# MCU_IO.net
KiCad netlist of a schematic drawn in Altium Designer
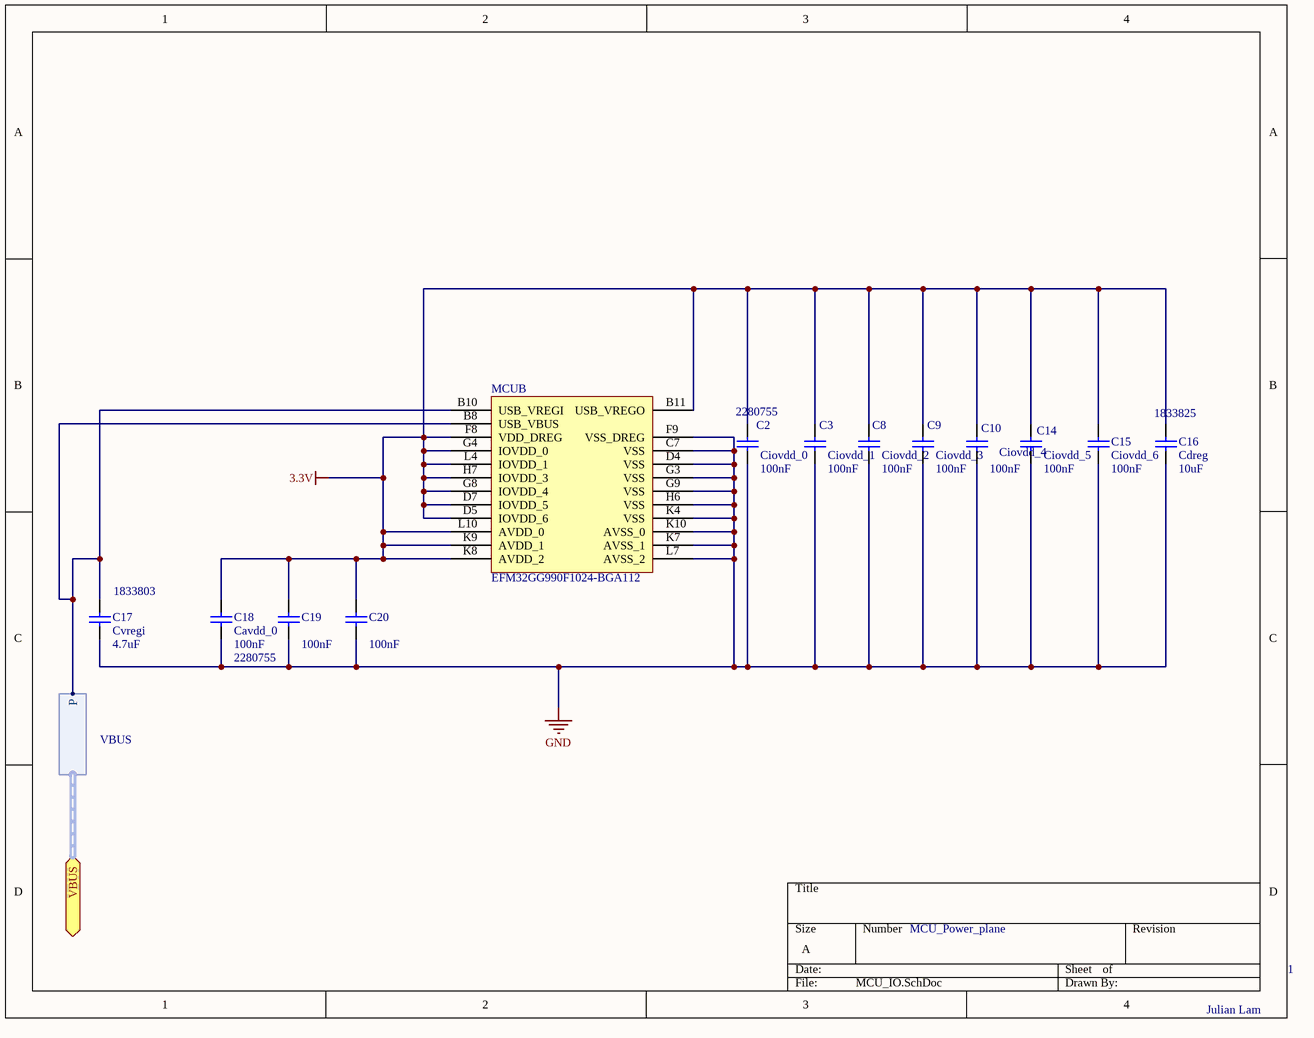
[diagram p0: MCU_IO.SchDoc]

(export (version "E")
  (design (tool "Eeschema 10.0.6"))
  (components
    (comp (ref "C2")
      (value "Ciovdd_0")
      (footprint "C1206")
      (description "Capacitor (Semiconductor SIM Model)")
      (fields
        (field (name "ALTIUM_VALUE") "100nF")
        (field (name "SUPPLIER PART NUMBER 1") "2280755")
        (field (name "MANUFACTURER") "AVX")
        (field (name "MANUFACTURER PART NUMBER") "02016D104KAT2A")
        (field (name "PUBLISHER") "Altium Limited")
      )
      (libsource (lib "Miscellaneous Devices") (part "Cap Semi"))
    )
    (comp (ref "C3")
      (value "Ciovdd_1")
      (footprint "C1206")
      (description "Capacitor (Semiconductor SIM Model)")
      (fields
        (field (name "ALTIUM_VALUE") "100nF")
        (field (name "MANUFACTURER") "AVX")
        (field (name "MANUFACTURER PART NUMBER") "02016D104KAT2A")
        (field (name "PUBLISHER") "Altium Limited")
      )
      (libsource (lib "Miscellaneous Devices") (part "Cap Semi"))
    )
    (comp (ref "C8")
      (value "Ciovdd_2")
      (footprint "C1206")
      (description "Capacitor (Semiconductor SIM Model)")
      (fields
        (field (name "ALTIUM_VALUE") "100nF")
        (field (name "MANUFACTURER") "AVX")
        (field (name "MANUFACTURER PART NUMBER") "02016D104KAT2A")
        (field (name "PUBLISHER") "Altium Limited")
      )
      (libsource (lib "Miscellaneous Devices") (part "Cap Semi"))
    )
    (comp (ref "C9")
      (value "Ciovdd_3")
      (footprint "C1206")
      (description "Capacitor (Semiconductor SIM Model)")
      (fields
        (field (name "ALTIUM_VALUE") "100nF")
        (field (name "MANUFACTURER") "AVX")
        (field (name "MANUFACTURER PART NUMBER") "02016D104KAT2A")
        (field (name "PUBLISHER") "Altium Limited")
      )
      (libsource (lib "Miscellaneous Devices") (part "Cap Semi"))
    )
    (comp (ref "C10")
      (value "Ciovdd_4")
      (footprint "C1206")
      (description "Capacitor (Semiconductor SIM Model)")
      (fields
        (field (name "ALTIUM_VALUE") "100nF")
        (field (name "MANUFACTURER") "AVX")
        (field (name "MANUFACTURER PART NUMBER") "02016D104KAT2A")
        (field (name "PUBLISHER") "Altium Limited")
      )
      (libsource (lib "Miscellaneous Devices") (part "Cap Semi"))
    )
    (comp (ref "C14")
      (value "Ciovdd_5")
      (footprint "C1206")
      (description "Capacitor (Semiconductor SIM Model)")
      (fields
        (field (name "ALTIUM_VALUE") "100nF")
        (field (name "MANUFACTURER") "AVX")
        (field (name "MANUFACTURER PART NUMBER") "02016D104KAT2A")
        (field (name "PUBLISHER") "Altium Limited")
      )
      (libsource (lib "Miscellaneous Devices") (part "Cap Semi"))
    )
    (comp (ref "C15")
      (value "Ciovdd_6")
      (footprint "C1206")
      (description "Capacitor (Semiconductor SIM Model)")
      (fields
        (field (name "ALTIUM_VALUE") "100nF")
        (field (name "MANUFACTURER") "AVX")
        (field (name "MANUFACTURER PART NUMBER") "02016D104KAT2A")
        (field (name "PUBLISHER") "Altium Limited")
      )
      (libsource (lib "Miscellaneous Devices") (part "Cap Semi"))
    )
    (comp (ref "C16")
      (value "Cdreg")
      (footprint "C1206")
      (description "Capacitor (Semiconductor SIM Model)")
      (fields
        (field (name "ALTIUM_VALUE") "10uF")
        (field (name "SUPPLIER PART NUMBER 1") "1833825")
        (field (name "MANUFACTURER") "AVX")
        (field (name "MANUFACTURER PART NUMBER") "12063D106KAT2A")
        (field (name "PUBLISHER") "Altium Limited")
      )
      (libsource (lib "Miscellaneous Devices") (part "Cap Semi"))
    )
    (comp (ref "C17")
      (value "Cvregi")
      (footprint "C1206")
      (description "Capacitor (Semiconductor SIM Model)")
      (fields
        (field (name "ALTIUM_VALUE") "4.7uF")
        (field (name "SUPPLIER PART NUMBER 1") "1833803")
        (field (name "MANUFACTURER") "AVX")
        (field (name "MANUFACTURER PART NUMBER") "06036D475KAT2A")
        (field (name "PUBLISHER") "Altium Limited")
      )
      (libsource (lib "Miscellaneous Devices") (part "Cap Semi"))
    )
    (comp (ref "C18")
      (value "Cavdd_0")
      (footprint "C1206")
      (description "Capacitor (Semiconductor SIM Model)")
      (fields
        (field (name "ALTIUM_VALUE") "100nF")
        (field (name "SUPPLIER PART NUMBER 1") "2280755")
        (field (name "MANUFACTURER") "AVX")
        (field (name "MANUFACTURER PART NUMBER") "02016D104KAT2A")
        (field (name "PUBLISHER") "Altium Limited")
      )
      (libsource (lib "Miscellaneous Devices") (part "Cap Semi"))
    )
    (comp (ref "C19")
      (value "100nF")
      (footprint "C1206")
      (description "Capacitor (Semiconductor SIM Model)")
      (fields
        (field (name "MANUFACTURER") "AVX")
        (field (name "MANUFACTURER PART NUMBER") "02016D104KAT2A")
        (field (name "PUBLISHER") "Altium Limited")
      )
      (libsource (lib "Miscellaneous Devices") (part "Cap Semi"))
    )
    (comp (ref "C20")
      (value "100nF")
      (footprint "C1206")
      (description "Capacitor (Semiconductor SIM Model)")
      (fields
        (field (name "MANUFACTURER") "AVX")
        (field (name "MANUFACTURER PART NUMBER") "02016D104KAT2A")
        (field (name "PUBLISHER") "Altium Limited")
      )
      (libsource (lib "Miscellaneous Devices") (part "Cap Semi"))
    )
    (comp (ref "MCU")
      (value "EFM32GG990F1024-BGA112")
      (footprint "ENMR-BGA112")
      (fields (field (name "GENERIC PART NUMBER") "EFM32GG990"))
      (libsource (lib "Altium Content Vault") (part "CMP-0270-00024-1"))
    )
  )
  (nets
    (net (code "3") (name "3.3V") (class "Default")
      (node (ref "C10") (pin "2") (pinfunction "2_2") (pintype "passive"))
      (node (ref "C14") (pin "2") (pinfunction "2_2") (pintype "passive"))
      (node (ref "C15") (pin "2") (pinfunction "2_2") (pintype "passive"))
      (node (ref "C16") (pin "2") (pinfunction "2_2") (pintype "passive"))
      (node (ref "C18") (pin "2") (pinfunction "2_2") (pintype "passive"))
      (node (ref "C19") (pin "2") (pinfunction "2_2") (pintype "passive"))
      (node (ref "C2") (pin "2") (pinfunction "2_2") (pintype "passive"))
      (node (ref "C20") (pin "1") (pinfunction "1_1") (pintype "passive"))
      (node (ref "C3") (pin "2") (pinfunction "2_2") (pintype "passive"))
      (node (ref "C8") (pin "2") (pinfunction "2_2") (pintype "passive"))
      (node (ref "C9") (pin "2") (pinfunction "2_2") (pintype "passive"))
      (node (ref "MCU") (pin "B11") (pinfunction "USB_VREGO_B11") (pintype "passive"))
      (node (ref "MCU") (pin "D5") (pinfunction "IOVDD_6_D5") (pintype "power_in"))
      (node (ref "MCU") (pin "D7") (pinfunction "IOVDD_5_D7") (pintype "power_in"))
      (node (ref "MCU") (pin "F8") (pinfunction "VDD_DREG_F8") (pintype "power_in"))
      (node (ref "MCU") (pin "G4") (pinfunction "IOVDD_0_G4") (pintype "power_in"))
      (node (ref "MCU") (pin "G8") (pinfunction "IOVDD_4_G8") (pintype "power_in"))
      (node (ref "MCU") (pin "H7") (pinfunction "IOVDD_3_H7") (pintype "power_in"))
      (node (ref "MCU") (pin "K8") (pinfunction "AVDD_2_K8") (pintype "power_in"))
      (node (ref "MCU") (pin "K9") (pinfunction "AVDD_1_K9") (pintype "power_in"))
      (node (ref "MCU") (pin "L10") (pinfunction "AVDD_0_L10") (pintype "power_in"))
      (node (ref "MCU") (pin "L4") (pinfunction "IOVDD_1_L4") (pintype "power_in"))
    )
    (net (code "4") (name "GND") (class "Default")
      (node (ref "C10") (pin "1") (pinfunction "1_1") (pintype "passive"))
      (node (ref "C14") (pin "1") (pinfunction "1_1") (pintype "passive"))
      (node (ref "C15") (pin "1") (pinfunction "1_1") (pintype "passive"))
      (node (ref "C16") (pin "1") (pinfunction "1_1") (pintype "passive"))
      (node (ref "C17") (pin "1") (pinfunction "1_1") (pintype "passive"))
      (node (ref "C18") (pin "1") (pinfunction "1_1") (pintype "passive"))
      (node (ref "C19") (pin "1") (pinfunction "1_1") (pintype "passive"))
      (node (ref "C2") (pin "1") (pinfunction "1_1") (pintype "passive"))
      (node (ref "C20") (pin "2") (pinfunction "2_2") (pintype "passive"))
      (node (ref "C3") (pin "1") (pinfunction "1_1") (pintype "passive"))
      (node (ref "C8") (pin "1") (pinfunction "1_1") (pintype "passive"))
      (node (ref "C9") (pin "1") (pinfunction "1_1") (pintype "passive"))
      (node (ref "MCU") (pin "C7") (pinfunction "VSS_C7") (pintype "power_in"))
      (node (ref "MCU") (pin "D4") (pinfunction "VSS_D4") (pintype "power_in"))
      (node (ref "MCU") (pin "F9") (pinfunction "VSS_DREG_F9") (pintype "power_in"))
      (node (ref "MCU") (pin "G3") (pinfunction "VSS_G3") (pintype "power_in"))
      (node (ref "MCU") (pin "G9") (pinfunction "VSS_G9") (pintype "power_in"))
      (node (ref "MCU") (pin "H6") (pinfunction "VSS_H6") (pintype "power_in"))
      (node (ref "MCU") (pin "K10") (pinfunction "AVSS_0_K10") (pintype "power_in"))
      (node (ref "MCU") (pin "K4") (pinfunction "VSS_K4") (pintype "power_in"))
      (node (ref "MCU") (pin "K7") (pinfunction "AVSS_1_K7") (pintype "power_in"))
      (node (ref "MCU") (pin "L7") (pinfunction "AVSS_2_L7") (pintype "power_in"))
    )
    (net (code "5") (name "Net-(MCUB-USB_VBUS)") (class "Default")
      (node (ref "C17") (pin "2") (pinfunction "2_2") (pintype "passive"))
      (node (ref "MCU") (pin "B10") (pinfunction "USB_VREGI_B10") (pintype "power_in"))
      (node (ref "MCU") (pin "B8") (pinfunction "USB_VBUS_B8") (pintype "power_in"))
    )
  )
)
